# PFC.net
KiCad netlist of a schematic drawn in Altium Designer
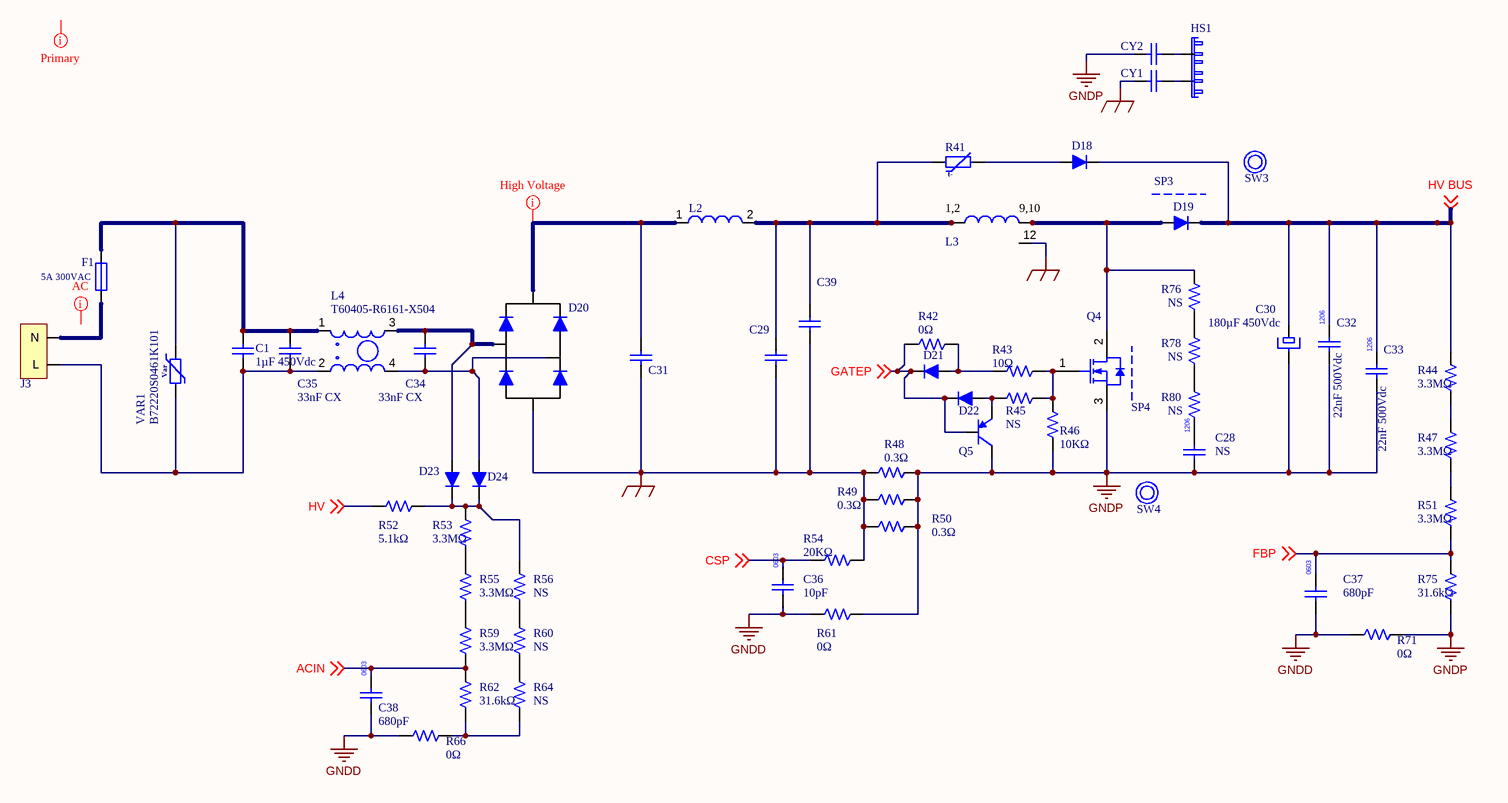
[diagram p0: PFC.SchDoc]

(export (version "E")
  (design (tool "Eeschema 10.0.6"))
  (components
    (comp (ref "C1")
      (value "1µF 450Vdc")
      (footprint "17.5x8.5x15 mm - Doble")
      (fields (field (name "Comment") "Capacitor_17.5x8.5x15 r15mm_Doble"))
      (libsource (lib "Charger") (part "Capacitor_17.5x8.5x15 r15mm_Doble"))
    )
    (comp (ref "C28")
      (value "NS")
      (footprint "CC/NM 1206")
      (description "22nF")
      (fields (field (name "Comment") "Capacitor 22nF"))
      (libsource (lib "Capacitors_1206") (part "Capacitor 22nF"))
    )
    (comp (ref "C29")
      (value "~")
      (footprint "TF684K2Y10BL270D9R")
      (libsource (lib "Charger") (part "TF684K2Y10BL270D9R"))
    )
    (comp (ref "C30")
      (value "180µF 450Vdc")
      (footprint "CER30x30")
      (libsource (lib "Charger") (part "Capacitor_30x30 r10"))
    )
    (comp (ref "C31")
      (value "~")
      (footprint "TF684K2Y10BL270D9R")
      (libsource (lib "Charger") (part "TF684K2Y10BL270D9R"))
    )
    (comp (ref "C32")
      (value "22nF 500Vdc")
      (footprint "CC/NM 1206")
      (description "22nF")
      (libsource (lib "Capacitors_1206") (part "Capacitor 22nF"))
    )
    (comp (ref "C33")
      (value "22nF 500Vdc")
      (footprint "CC/NM 1206")
      (description "22nF")
      (libsource (lib "Capacitors_1206") (part "Capacitor 22nF"))
    )
    (comp (ref "C34")
      (value "33nF CX")
      (footprint "POL 10.3x5x10.5 R7.5")
      (fields (field (name "Comment") "MKS4J023302E00KSSD"))
      (libsource (lib "Charger") (part "Capacitor_10.3x5x10.5 r7.5mm"))
    )
    (comp (ref "C35")
      (value "33nF CX")
      (footprint "POL 10.3x5x10.5 R7.5")
      (fields (field (name "Comment") "MKS4J023302E00KSSD"))
      (libsource (lib "Charger") (part "Capacitor_10.3x5x10.5 r7.5mm"))
    )
    (comp (ref "C36")
      (value "10pF")
      (footprint "CC/NM 0603")
      (libsource (lib "Capacitors_0603") (part "Capacitor 220pF"))
    )
    (comp (ref "C37")
      (value "680pF")
      (footprint "CC/NM 0603")
      (libsource (lib "Capacitors_0603") (part "Capacitor 680pF"))
    )
    (comp (ref "C38")
      (value "680pF")
      (footprint "CC/NM 0603")
      (libsource (lib "Capacitors_0603") (part "Capacitor 680pF"))
    )
    (comp (ref "C39")
      (value "~")
      (footprint "17.5x8.5x15 mm")
      (libsource (lib "Charger") (part "Capacitor_17.5x8.5x15 r15mm"))
    )
    (comp (ref "CY1")
      (value "~")
      (footprint "C_Y_r10mm (2)")
      (libsource (lib "Charger") (part "Capacitor_Y_r10 (2)"))
    )
    (comp (ref "CY2")
      (value "~")
      (footprint "C_Y_r10mm (2)")
      (libsource (lib "Charger") (part "Capacitor_Y_r10 (2)"))
    )
    (comp (ref "D18")
      (value "~")
      (footprint "DO-214AC")
      (description "Fast Rectifier 600 V, 1 A, 1.3 V, 250 ns, 30 A")
      (libsource (lib "Charger") (part "RS1J"))
    )
    (comp (ref "D19")
      (value "~")
      (footprint "TO-220AC")
      (description "600 V, 8 A H-Series PFC Diode")
      (libsource (lib "Charger") (part "QH08TZ600"))
    )
    (comp (ref "D20")
      (value "~")
      (footprint "GBU4L")
      (description "Rectifier Diode, 600 V, 8 A, SIP, 1 V, 4 Pins")
      (libsource (lib "Charger") (part "Bridge_Rectifier"))
    )
    (comp (ref "D21")
      (value "~")
      (footprint "SODFL260X90-2N")
      (description "1N4148  miniMelf Series 500 mW 100 V Max Reverse Voltage 200 mA Small Signal Diode -")
      (libsource (lib "Charger") (part "1N4148WS"))
    )
    (comp (ref "D22")
      (value "~")
      (footprint "SODFL260X90-2N")
      (description "1N4148  miniMelf Series 500 mW 100 V Max Reverse Voltage 200 mA Small Signal Diode -")
      (libsource (lib "Charger") (part "1N4148WS"))
    )
    (comp (ref "D23") (value "~") (footprint "DIOMELF3516N") (libsource (lib "Charger") (part "WSGC10DH")))
    (comp (ref "D24") (value "~") (footprint "DIOMELF3516N") (libsource (lib "Charger") (part "WSGC10DH")))
    (comp (ref "F1")
      (value "5A 300VAC")
      (footprint "FUSE")
      (description "Fuse,  PCB, 5 A, 300 VAC, Serie SS-5H.")
      (libsource (lib "Charger") (part "SS-5H-5A-APH"))
    )
    (comp (ref "HS1") (value "~") (footprint "HS1") (libsource (lib "Charger") (part "HS1")))
    (comp (ref "J3")
      (value "~")
      (footprint "RAPC322X")
      (description "AC C8 Connector 250 V / 2.5 A")
      (libsource (lib "Charger") (part "Connector_AC"))
    )
    (comp (ref "L2")
      (value "~")
      (footprint "O 25x10")
      (libsource (lib "Charger") (part "Inductance_O 26-12"))
    )
    (comp (ref "L3") (value "~") (footprint "PQ 32/30") (libsource (lib "Charger") (part "Inductor_PQ32/30")))
    (comp (ref "L4")
      (value "T60405-R6161-X504")
      (footprint "T60405-R6161-X504")
      (description "CM Filter VAC 2x28.3mH@10kHz  5A")
      (libsource (lib "Charger") (part "T60405-R6161-X504"))
    )
    (comp (ref "Q4")
      (value "~")
      (footprint "TO-220 Shifted")
      (description "600V / 16A")
      (libsource (lib "Charger") (part "IPP60R600C6XKSA1"))
    )
    (comp (ref "Q5")
      (value "~")
      (footprint "SOT95P237X112-3N")
      (libsource (lib "Charger") (part "BJT_PNP_SOT23"))
    )
    (comp (ref "R41")
      (value "~")
      (footprint "NTC D2-10")
      (description "Termistor, NTC ICL, 2 ohm, -20% a +20%, , Serie SL22")
      (libsource (lib "Charger") (part "SL22 2R018"))
    )
    (comp (ref "R42")
      (value "0Ω")
      (footprint "CC/NM 0603")
      (description "Resistor 0603")
      (libsource (lib "Resistors_0603") (part "Resistor 0"))
    )
    (comp (ref "R43")
      (value "10Ω")
      (footprint "CC/NM 0603")
      (description "Resistor 0603")
      (libsource (lib "Resistors_0603") (part "Resistor 10"))
    )
    (comp (ref "R44")
      (value "3.3MΩ")
      (footprint "CC/NM 1206")
      (description "Resistor 1206")
      (libsource (lib "Resistors_1206") (part "Resistor 3M3"))
    )
    (comp (ref "R45")
      (value "NS")
      (footprint "CC/NM 0603")
      (description "Resistor 0603")
      (libsource (lib "Resistors_0603") (part "Resistor 4.7"))
    )
    (comp (ref "R46")
      (value "10KΩ")
      (footprint "CC/NM 0603")
      (description "Resistor 0603")
      (libsource (lib "Resistors_0603") (part "Resistor 10K"))
    )
    (comp (ref "R47")
      (value "3.3MΩ")
      (footprint "CC/NM 1206")
      (description "Resistor 1206")
      (libsource (lib "Resistors_1206") (part "Resistor 3M3"))
    )
    (comp (ref "R48")
      (value "0.3Ω")
      (footprint "CC/NM 2512")
      (description "Resistor 2512")
      (libsource (lib "Resistors_2512") (part "Resistor 1"))
    )
    (comp (ref "R49")
      (value "0.3Ω")
      (footprint "CC/NM 2512")
      (description "Resistor 2512")
      (libsource (lib "Resistors_2512") (part "Resistor 1"))
    )
    (comp (ref "R50")
      (value "0.3Ω")
      (footprint "CC/NM 2512")
      (description "Resistor 2512")
      (libsource (lib "Resistors_2512") (part "Resistor 1"))
    )
    (comp (ref "R51")
      (value "3.3MΩ")
      (footprint "CC/NM 1206")
      (description "Resistor 1206")
      (libsource (lib "Resistors_1206") (part "Resistor 3M3"))
    )
    (comp (ref "R52")
      (value "5.1kΩ")
      (footprint "CC/NM 1206")
      (description "Resistor 1206")
      (libsource (lib "Resistors_1206") (part "Resistor 5K1"))
    )
    (comp (ref "R53")
      (value "3.3MΩ")
      (footprint "CC/NM 1206")
      (description "Resistor 1206")
      (libsource (lib "Resistors_1206") (part "Resistor 3M3"))
    )
    (comp (ref "R54")
      (value "20KΩ")
      (footprint "CC/NM 0603")
      (description "Resistor 0603")
      (fields (field (name "Comment") "Resistor 20K"))
      (libsource (lib "Resistors_0603") (part "Resistor 20K"))
    )
    (comp (ref "R55")
      (value "3.3MΩ")
      (footprint "CC/NM 1206")
      (description "Resistor 1206")
      (libsource (lib "Resistors_1206") (part "Resistor 3M3"))
    )
    (comp (ref "R56")
      (value "NS")
      (footprint "CC/NM 1206")
      (description "Resistor 1206")
      (libsource (lib "Resistors_1206") (part "Resistor 3M3"))
    )
    (comp (ref "R59")
      (value "3.3MΩ")
      (footprint "CC/NM 1206")
      (description "Resistor 1206")
      (libsource (lib "Resistors_1206") (part "Resistor 3M3"))
    )
    (comp (ref "R60")
      (value "NS")
      (footprint "CC/NM 1206")
      (description "Resistor 1206")
      (libsource (lib "Resistors_1206") (part "Resistor 3M3"))
    )
    (comp (ref "R61")
      (value "0Ω")
      (footprint "CC/NM 0603")
      (description "Resistor 0603")
      (libsource (lib "Resistors_0603") (part "Resistor 1K"))
    )
    (comp (ref "R62")
      (value "31.6kΩ")
      (footprint "CC/NM 0603")
      (description "Resistor 0603")
      (fields (field (name "Comment") "Resistor 1K"))
      (libsource (lib "Resistors_0603") (part "Resistor 31K6"))
    )
    (comp (ref "R64")
      (value "NS")
      (footprint "CC/NM 1206")
      (description "Resistor 1206")
      (libsource (lib "Resistors_1206") (part "Resistor 3M3"))
    )
    (comp (ref "R66")
      (value "0Ω")
      (footprint "CC/NM 0603")
      (description "Resistor 0603")
      (libsource (lib "Resistors_0603") (part "Resistor 0"))
    )
    (comp (ref "R71")
      (value "0Ω")
      (footprint "CC/NM 0603")
      (description "Resistor 0603")
      (libsource (lib "Resistors_0603") (part "Resistor 0"))
    )
    (comp (ref "R75")
      (value "31.6kΩ")
      (footprint "CC/NM 0603")
      (description "Resistor 0603")
      (libsource (lib "Resistors_0603") (part "Resistor 31K6"))
    )
    (comp (ref "R76")
      (value "NS")
      (footprint "CC/NM 1206")
      (description "Resistor 1206")
      (fields (field (name "Comment") "Resistor 4.7"))
      (libsource (lib "Resistors_1206") (part "Resistor 4.7"))
    )
    (comp (ref "R78")
      (value "NS")
      (footprint "CC/NM 1206")
      (description "Resistor 1206")
      (fields (field (name "Comment") "Resistor 4.7"))
      (libsource (lib "Resistors_1206") (part "Resistor 4.7"))
    )
    (comp (ref "R80")
      (value "NS")
      (footprint "CC/NM 1206")
      (description "Resistor 1206")
      (fields (field (name "Comment") "Resistor 4.7"))
      (libsource (lib "Resistors_1206") (part "Resistor 4.7"))
    )
    (comp (ref "SP3") (value "SIL-PAD TO-220") (libsource (lib "Charger") (part "SIL-PAD TO-220")))
    (comp (ref "SP4") (value "SIL-PAD TO-220") (libsource (lib "Charger") (part "SIL-PAD TO-220")))
    (comp (ref "SW3")
      (value "Shoulder Washer M2.5")
      (libsource (lib "Charger") (part "Shoulder Washer M2.5"))
    )
    (comp (ref "SW4")
      (value "Shoulder Washer M2.5")
      (libsource (lib "Charger") (part "Shoulder Washer M2.5"))
    )
    (comp (ref "VAR1")
      (value "B72220S0461K101")
      (footprint "Var 10mm")
      (description "Varistor  (TVS), 460 V, 615 V, Serial B722, 1240 V, Disc 20mm")
      (libsource (lib "Charger") (part "B72220S0461K101"))
    )
  )
  (nets
    (net (code "1") (name "ACIN") (class "Default")
      (node (ref "C38") (pin "1") (pinfunction "1_1") (pintype "passive"))
      (node (ref "R59") (pin "1") (pinfunction "1_1") (pintype "passive"))
      (node (ref "R62") (pin "2") (pinfunction "2_2") (pintype "passive"))
    )
    (net (code "2") (name "CSP") (class "Default")
      (node (ref "C36") (pin "1") (pinfunction "1_1") (pintype "passive"))
      (node (ref "R54") (pin "1") (pinfunction "1_1") (pintype "passive"))
    )
    (net (code "3") (name "EARTH") (class "Default")
      (node (ref "C29") (pin "2") (pinfunction "2_2") (pintype "passive"))
      (node (ref "C31") (pin "2") (pinfunction "2_2") (pintype "passive"))
      (node (ref "C39") (pin "2") (pinfunction "2_2") (pintype "passive"))
      (node (ref "CY1") (pin "1") (pinfunction "1_1") (pintype "passive"))
      (node (ref "D20") (pin "4") (pinfunction "-_4") (pintype "passive"))
      (node (ref "L3") (pin "12") (pinfunction "12_12") (pintype "passive"))
      (node (ref "R48") (pin "1") (pinfunction "1_1") (pintype "passive"))
      (node (ref "R49") (pin "1") (pinfunction "1_1") (pintype "passive"))
      (node (ref "R50") (pin "1") (pinfunction "1_1") (pintype "passive"))
      (node (ref "R54") (pin "2") (pinfunction "2_2") (pintype "passive"))
    )
    (net (code "4") (name "FBP") (class "Default")
      (node (ref "C37") (pin "1") (pinfunction "1_1") (pintype "passive"))
      (node (ref "R51") (pin "1") (pinfunction "1_1") (pintype "passive"))
      (node (ref "R75") (pin "2") (pinfunction "2_2") (pintype "passive"))
    )
    (net (code "5") (name "GATEP") (class "Default")
      (node (ref "D21") (pin "1") (pinfunction "1_1") (pintype "passive"))
      (node (ref "D22") (pin "1") (pinfunction "1_1") (pintype "passive"))
      (node (ref "Q5") (pin "1") (pinfunction "B_1") (pintype "passive"))
      (node (ref "R42") (pin "1") (pinfunction "1_1") (pintype "passive"))
    )
    (net (code "6") (name "GNDD") (class "Default")
      (node (ref "C36") (pin "2") (pinfunction "2_2") (pintype "passive"))
      (node (ref "C37") (pin "2") (pinfunction "2_2") (pintype "passive"))
      (node (ref "C38") (pin "2") (pinfunction "2_2") (pintype "passive"))
      (node (ref "R61") (pin "1") (pinfunction "1_1") (pintype "passive"))
      (node (ref "R66") (pin "1") (pinfunction "1_1") (pintype "passive"))
      (node (ref "R71") (pin "1") (pinfunction "1_1") (pintype "passive"))
    )
    (net (code "7") (name "GNDP") (class "Default")
      (node (ref "C28") (pin "2") (pinfunction "2_2") (pintype "passive"))
      (node (ref "C30") (pin "2") (pinfunction "2_2") (pintype "passive"))
      (node (ref "C32") (pin "2") (pinfunction "2_2") (pintype "passive"))
      (node (ref "C33") (pin "2") (pinfunction "2_2") (pintype "passive"))
      (node (ref "CY2") (pin "1") (pinfunction "1_1") (pintype "passive"))
      (node (ref "Q4") (pin "3") (pinfunction "SOURCE_3") (pintype "passive"))
      (node (ref "Q5") (pin "3") (pinfunction "C_3") (pintype "passive"))
      (node (ref "R46") (pin "1") (pinfunction "1_1") (pintype "passive"))
      (node (ref "R48") (pin "2") (pinfunction "2_2") (pintype "passive"))
      (node (ref "R49") (pin "2") (pinfunction "2_2") (pintype "passive"))
      (node (ref "R50") (pin "2") (pinfunction "2_2") (pintype "passive"))
      (node (ref "R61") (pin "2") (pinfunction "2_2") (pintype "passive"))
      (node (ref "R71") (pin "2") (pinfunction "2_2") (pintype "passive"))
      (node (ref "R75") (pin "1") (pinfunction "1_1") (pintype "passive"))
    )
    (net (code "8") (name "HV") (class "Default")
      (node (ref "R52") (pin "1") (pinfunction "1_1") (pintype "passive"))
    )
    (net (code "9") (name "HV BUS") (class "Default")
      (node (ref "C30") (pin "1") (pinfunction "1_1") (pintype "passive"))
      (node (ref "C32") (pin "1") (pinfunction "1_1") (pintype "passive"))
      (node (ref "C33") (pin "1") (pinfunction "1_1") (pintype "passive"))
      (node (ref "D18") (pin "1") (pinfunction "1_1") (pintype "passive"))
      (node (ref "D19") (pin "1") (pinfunction "K_1") (pintype "passive"))
      (node (ref "R44") (pin "2") (pinfunction "2_2") (pintype "passive"))
    )
    (net (code "10") (name "Net-(C1-Pad2)") (class "Default")
      (node (ref "C1") (pin "2") (pinfunction "2_2") (pintype "passive"))
      (node (ref "C1") (pin "3") (pinfunction "3_3") (pintype "passive"))
      (node (ref "C35") (pin "1") (pinfunction "1_1") (pintype "passive"))
      (node (ref "F1") (pin "1") (pinfunction "1_1") (pintype "passive"))
      (node (ref "L4") (pin "1") (pinfunction "1_1") (pintype "passive"))
      (node (ref "VAR1") (pin "2") (pinfunction "2_2") (pintype "passive"))
    )
    (net (code "11") (name "Net-(C28-Pad1)") (class "Default")
      (node (ref "C28") (pin "1") (pinfunction "1_1") (pintype "passive"))
      (node (ref "R80") (pin "1") (pinfunction "1_1") (pintype "passive"))
    )
    (net (code "12") (name "Net-(C29-Pad1)") (class "Default")
      (node (ref "C29") (pin "1") (pinfunction "1_1") (pintype "passive"))
      (node (ref "C39") (pin "1") (pinfunction "1_1") (pintype "passive"))
      (node (ref "L2") (pin "2") (pinfunction "2_2") (pintype "passive"))
      (node (ref "L3") (pin "1") (pinfunction "1_1") (pintype "passive"))
      (node (ref "L3") (pin "2") (pinfunction "2_2") (pintype "passive"))
      (node (ref "R41") (pin "1") (pinfunction "1_1") (pintype "passive"))
    )
    (net (code "13") (name "Net-(C34-Pad1)") (class "Default")
      (node (ref "C34") (pin "1") (pinfunction "1_1") (pintype "passive"))
      (node (ref "D20") (pin "3") (pinfunction "AC_3") (pintype "passive"))
      (node (ref "D23") (pin "2") (pinfunction "2_2") (pintype "passive"))
      (node (ref "L4") (pin "3") (pinfunction "3_3") (pintype "passive"))
    )
    (net (code "14") (name "Net-(C34-Pad2)") (class "Default")
      (node (ref "C34") (pin "2") (pinfunction "2_2") (pintype "passive"))
      (node (ref "D20") (pin "2") (pinfunction "AC_2") (pintype "passive"))
      (node (ref "D24") (pin "2") (pinfunction "2_2") (pintype "passive"))
      (node (ref "L4") (pin "4") (pinfunction "4_4") (pintype "passive"))
    )
    (net (code "15") (name "Net-(CY1-Pad2)") (class "Default")
      (node (ref "CY1") (pin "2") (pinfunction "2_2") (pintype "passive"))
      (node (ref "HS1") (pin "0") (pinfunction "0_0") (pintype "passive"))
    )
    (net (code "16") (name "Net-(CY2-Pad2)") (class "Default")
      (node (ref "CY2") (pin "2") (pinfunction "2_2") (pintype "passive"))
      (node (ref "HS1") (pin "1") (pinfunction "1_1") (pintype "passive"))
    )
    (net (code "17") (name "Net-(D18-Pad2)") (class "Default")
      (node (ref "D18") (pin "2") (pinfunction "2_2") (pintype "passive"))
      (node (ref "R41") (pin "2") (pinfunction "2_2") (pintype "passive"))
    )
    (net (code "18") (name "Net-(D19-A)") (class "Default")
      (node (ref "D19") (pin "2") (pinfunction "A_2") (pintype "passive"))
      (node (ref "L3") (pin "10") (pinfunction "10_10") (pintype "passive"))
      (node (ref "L3") (pin "9") (pinfunction "9_9") (pintype "passive"))
      (node (ref "Q4") (pin "2") (pinfunction "DRAIN_2") (pintype "passive"))
      (node (ref "R76") (pin "2") (pinfunction "2_2") (pintype "passive"))
    )
    (net (code "19") (name "Net-(D20-+)") (class "Default")
      (node (ref "C31") (pin "1") (pinfunction "1_1") (pintype "passive"))
      (node (ref "D20") (pin "1") (pinfunction "+_1") (pintype "passive"))
      (node (ref "L2") (pin "1") (pinfunction "1_1") (pintype "passive"))
    )
    (net (code "20") (name "Net-(D21-Pad2)") (class "Default")
      (node (ref "D21") (pin "2") (pinfunction "2_2") (pintype "passive"))
      (node (ref "R42") (pin "2") (pinfunction "2_2") (pintype "passive"))
      (node (ref "R43") (pin "1") (pinfunction "1_1") (pintype "passive"))
    )
    (net (code "21") (name "Net-(D23-Pad1)") (class "Default")
      (node (ref "D23") (pin "1") (pinfunction "1_1") (pintype "passive"))
      (node (ref "D24") (pin "1") (pinfunction "1_1") (pintype "passive"))
      (node (ref "R52") (pin "2") (pinfunction "2_2") (pintype "passive"))
      (node (ref "R53") (pin "2") (pinfunction "2_2") (pintype "passive"))
      (node (ref "R56") (pin "2") (pinfunction "2_2") (pintype "passive"))
    )
    (net (code "22") (name "Net-(J3-L)") (class "Default")
      (node (ref "C1") (pin "1") (pinfunction "1_1") (pintype "passive"))
      (node (ref "C35") (pin "2") (pinfunction "2_2") (pintype "passive"))
      (node (ref "J3") (pin "1") (pinfunction "L_1") (pintype "passive"))
      (node (ref "L4") (pin "2") (pinfunction "2_2") (pintype "passive"))
      (node (ref "VAR1") (pin "1") (pinfunction "1_1") (pintype "passive"))
    )
    (net (code "23") (name "Net-(J3-N)") (class "Default")
      (node (ref "F1") (pin "2") (pinfunction "2_2") (pintype "passive"))
      (node (ref "J3") (pin "2") (pinfunction "N_2") (pintype "passive"))
    )
    (net (code "24") (name "Net-(Q4-GATE)") (class "Default")
      (node (ref "Q4") (pin "1") (pinfunction "GATE_1") (pintype "passive"))
      (node (ref "R43") (pin "2") (pinfunction "2_2") (pintype "passive"))
      (node (ref "R45") (pin "2") (pinfunction "2_2") (pintype "passive"))
      (node (ref "R46") (pin "2") (pinfunction "2_2") (pintype "passive"))
    )
    (net (code "25") (name "Net-(Q5-E)") (class "Default")
      (node (ref "D22") (pin "2") (pinfunction "2_2") (pintype "passive"))
      (node (ref "Q5") (pin "2") (pinfunction "E_2") (pintype "passive"))
      (node (ref "R45") (pin "1") (pinfunction "1_1") (pintype "passive"))
    )
    (net (code "26") (name "Net-(R44-Pad1)") (class "Default")
      (node (ref "R44") (pin "1") (pinfunction "1_1") (pintype "passive"))
      (node (ref "R47") (pin "2") (pinfunction "2_2") (pintype "passive"))
    )
    (net (code "27") (name "Net-(R47-Pad1)") (class "Default")
      (node (ref "R47") (pin "1") (pinfunction "1_1") (pintype "passive"))
      (node (ref "R51") (pin "2") (pinfunction "2_2") (pintype "passive"))
    )
    (net (code "28") (name "Net-(R53-Pad1)") (class "Default")
      (node (ref "R53") (pin "1") (pinfunction "1_1") (pintype "passive"))
      (node (ref "R55") (pin "2") (pinfunction "2_2") (pintype "passive"))
    )
    (net (code "29") (name "Net-(R55-Pad1)") (class "Default")
      (node (ref "R55") (pin "1") (pinfunction "1_1") (pintype "passive"))
      (node (ref "R59") (pin "2") (pinfunction "2_2") (pintype "passive"))
    )
    (net (code "30") (name "Net-(R56-Pad1)") (class "Default")
      (node (ref "R56") (pin "1") (pinfunction "1_1") (pintype "passive"))
      (node (ref "R60") (pin "2") (pinfunction "2_2") (pintype "passive"))
    )
    (net (code "31") (name "Net-(R60-Pad1)") (class "Default")
      (node (ref "R60") (pin "1") (pinfunction "1_1") (pintype "passive"))
      (node (ref "R64") (pin "2") (pinfunction "2_2") (pintype "passive"))
    )
    (net (code "32") (name "Net-(R62-Pad1)") (class "Default")
      (node (ref "R62") (pin "1") (pinfunction "1_1") (pintype "passive"))
      (node (ref "R64") (pin "1") (pinfunction "1_1") (pintype "passive"))
      (node (ref "R66") (pin "2") (pinfunction "2_2") (pintype "passive"))
    )
    (net (code "33") (name "Net-(R76-Pad1)") (class "Default")
      (node (ref "R76") (pin "1") (pinfunction "1_1") (pintype "passive"))
      (node (ref "R78") (pin "2") (pinfunction "2_2") (pintype "passive"))
    )
    (net (code "34") (name "Net-(R78-Pad1)") (class "Default")
      (node (ref "R78") (pin "1") (pinfunction "1_1") (pintype "passive"))
      (node (ref "R80") (pin "2") (pinfunction "2_2") (pintype "passive"))
    )
  )
)
